# MaTouch_DevKit_1_28_Controller_V1_1.net
KiCad netlist of a schematic drawn in EAGLE
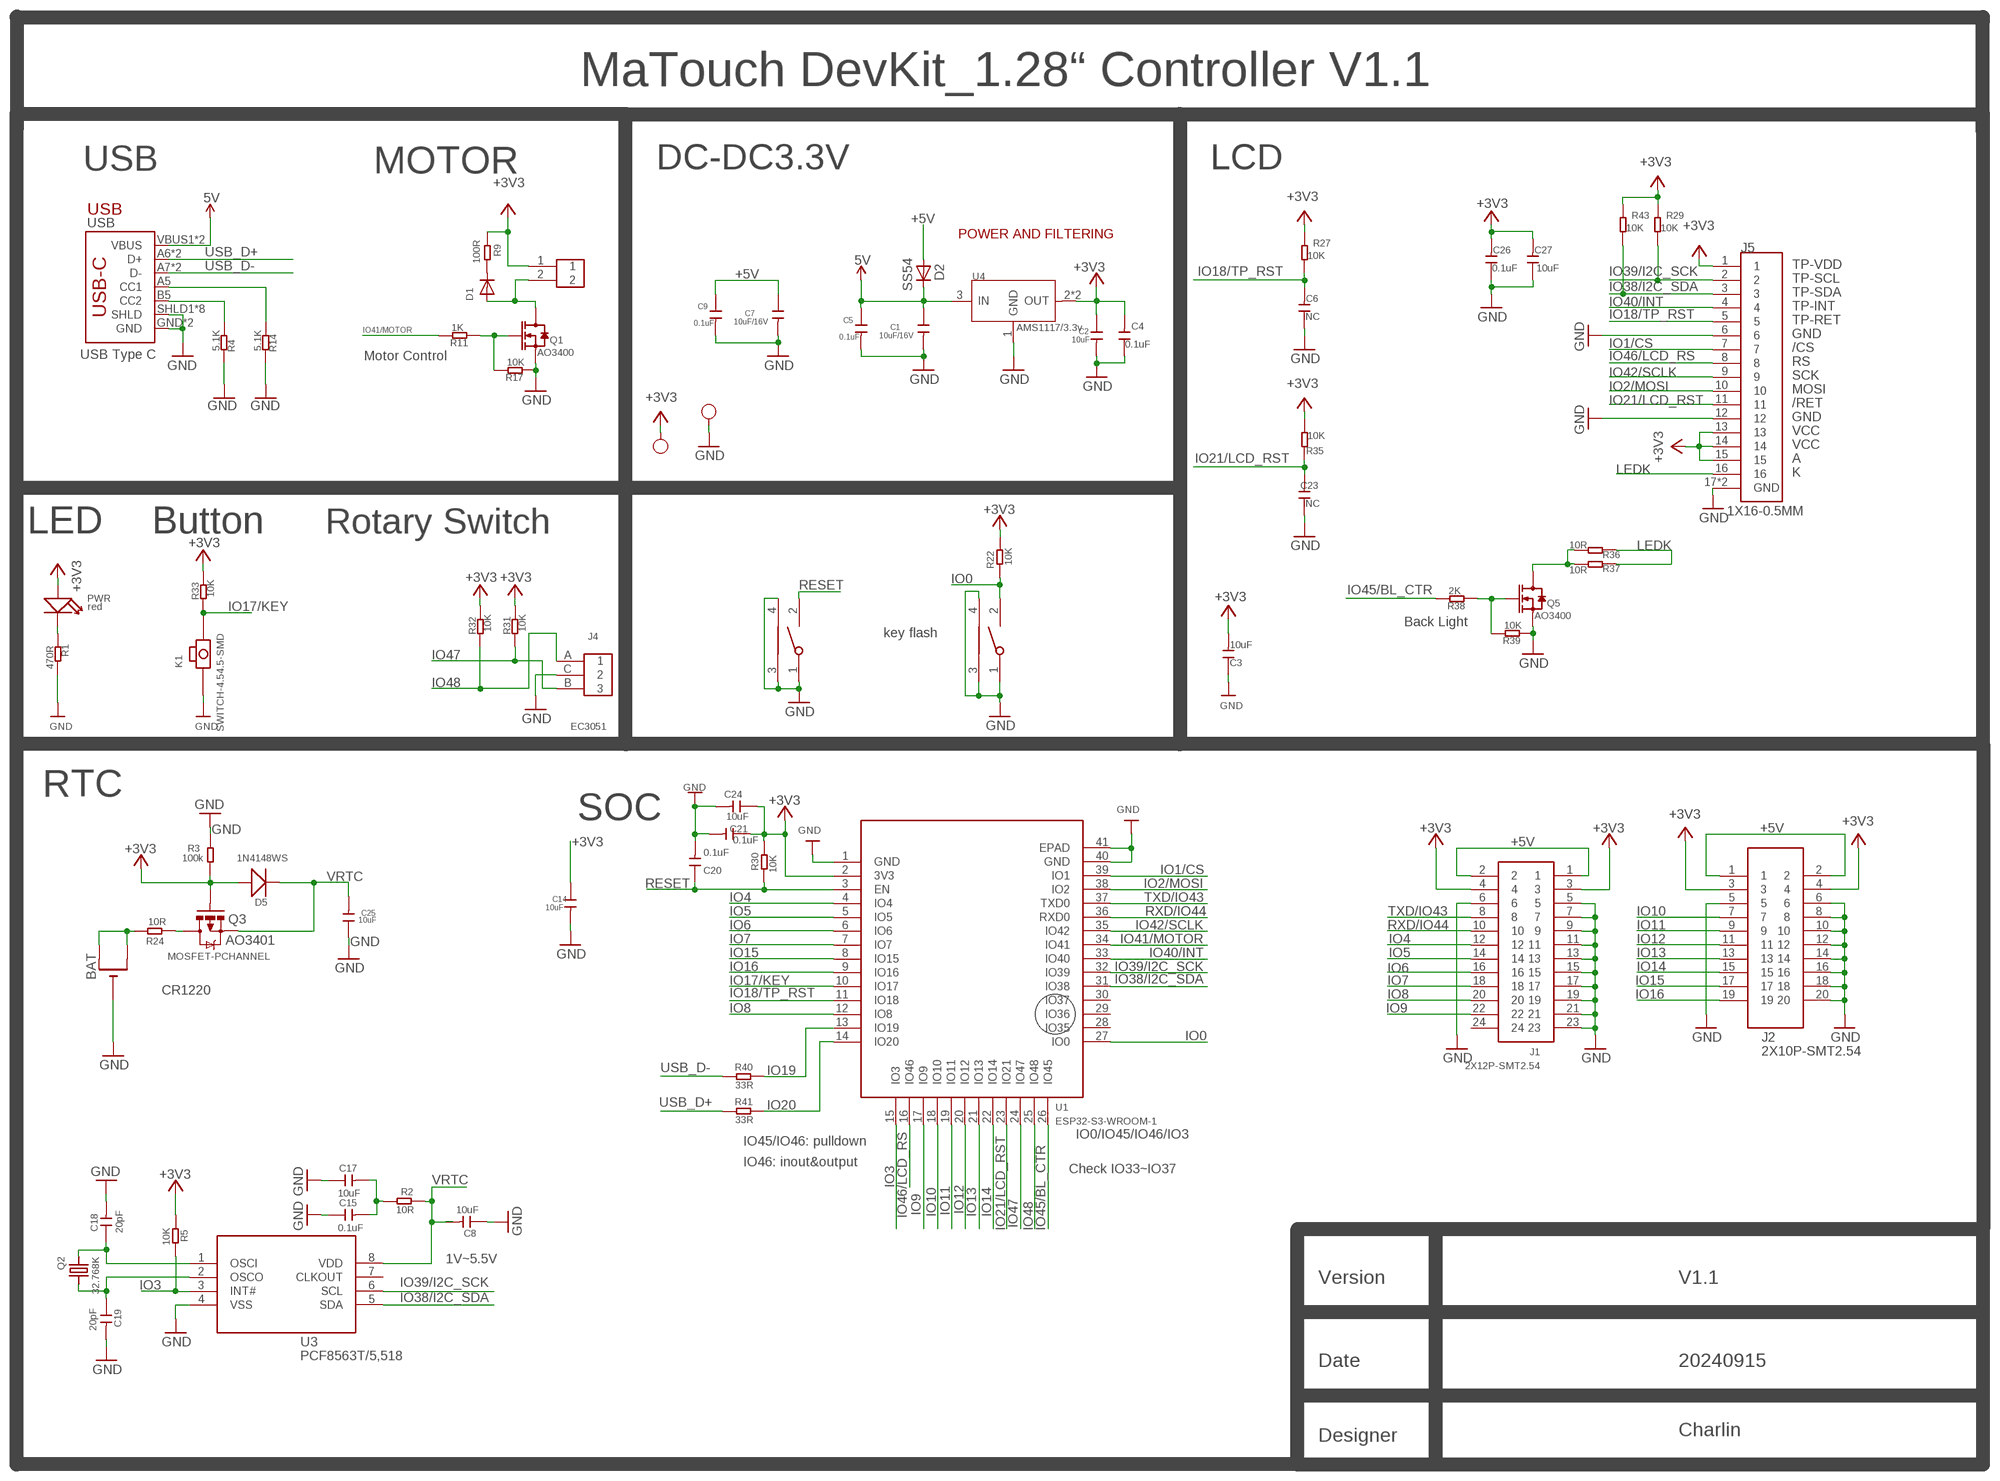
[diagram p0: schematic, sheet 1]

(export (version "E")
  (design (tool "Eeschema 10.0.6"))
  (components
    (comp (ref "3V3")
      (value "TEST-POINT'4545'")
      (footprint "eagle-import:TP-D45MIL")
      (fields (field (name "PARTNO") "DNP") (field (name "PARTNO_1") "DNP"))
      (libsource (lib "eagle-import") (part "TEST-POINT'4545'"))
    )
    (comp (ref "BAT")
      (value "CR1220SMT")
      (footprint "eagle-import:CR1220-SMD")
      (libsource (lib "eagle-import") (part "CR1220SMT"))
    )
    (comp (ref "BOOT")
      (value "TS24CA")
      (footprint "eagle-import:2_4_3.5MM")
      (libsource (lib "eagle-import") (part "TS24CA"))
    )
    (comp (ref "C1")
      (value "10uF/16V")
      (footprint "eagle-import:0603")
      (libsource (lib "eagle-import") (part "C-0603"))
    )
    (comp (ref "C2")
      (value "10uF")
      (footprint "eagle-import:0603")
      (libsource (lib "eagle-import") (part "C-0603"))
    )
    (comp (ref "C3")
      (value "10uF")
      (footprint "eagle-import:DISCRETE_C0603")
      (libsource (lib "eagle-import") (part "DISCRETE_C-0603"))
    )
    (comp (ref "C4")
      (value "0.1uF")
      (footprint "eagle-import:DISCRETE_C0402")
      (libsource (lib "eagle-import") (part "DISCRETE_C-0402"))
    )
    (comp (ref "C5")
      (value "0.1uF")
      (footprint "eagle-import:0603")
      (libsource (lib "eagle-import") (part "C-0603"))
    )
    (comp (ref "C6")
      (value "NC")
      (footprint "eagle-import:DISCRETE_C0402")
      (libsource (lib "eagle-import") (part "DISCRETE_C-0402"))
    )
    (comp (ref "C7")
      (value "10uF/16V")
      (footprint "eagle-import:0603")
      (libsource (lib "eagle-import") (part "C-0603"))
    )
    (comp (ref "C8")
      (value "10uF")
      (footprint "eagle-import:DISCRETE_C0603")
      (libsource (lib "eagle-import") (part "DISCRETE_C-0603"))
    )
    (comp (ref "C9")
      (value "0.1uF")
      (footprint "eagle-import:0603")
      (libsource (lib "eagle-import") (part "C-0603"))
    )
    (comp (ref "C14")
      (value "10uF")
      (footprint "eagle-import:0603")
      (libsource (lib "eagle-import") (part "C-0603"))
    )
    (comp (ref "C15")
      (value "0.1uF")
      (footprint "eagle-import:DISCRETE_C0603")
      (libsource (lib "eagle-import") (part "DISCRETE_C-0603"))
    )
    (comp (ref "C17")
      (value "10uF")
      (footprint "eagle-import:DISCRETE_C0603")
      (libsource (lib "eagle-import") (part "DISCRETE_C-0603"))
    )
    (comp (ref "C18")
      (value "20pF")
      (footprint "eagle-import:DISCRETE_C0603")
      (libsource (lib "eagle-import") (part "DISCRETE_C-0603"))
    )
    (comp (ref "C19")
      (value "20pF")
      (footprint "eagle-import:DISCRETE_C0603")
      (libsource (lib "eagle-import") (part "DISCRETE_C-0603"))
    )
    (comp (ref "C20")
      (value "0.1uF")
      (footprint "eagle-import:DISCRETE_C0603")
      (libsource (lib "eagle-import") (part "DISCRETE_C-0603"))
    )
    (comp (ref "C21")
      (value "0.1uF")
      (footprint "eagle-import:DISCRETE_C0603")
      (libsource (lib "eagle-import") (part "DISCRETE_C-0603"))
    )
    (comp (ref "C23")
      (value "NC")
      (footprint "eagle-import:DISCRETE_C0402")
      (libsource (lib "eagle-import") (part "DISCRETE_C-0402"))
    )
    (comp (ref "C24")
      (value "10uF")
      (footprint "eagle-import:DISCRETE_C0603")
      (libsource (lib "eagle-import") (part "DISCRETE_C-0603"))
    )
    (comp (ref "C25")
      (value "10uF")
      (footprint "eagle-import:0603")
      (libsource (lib "eagle-import") (part "C-0603"))
    )
    (comp (ref "C26")
      (value "0.1uF")
      (footprint "eagle-import:DISCRETE_C0402")
      (libsource (lib "eagle-import") (part "DISCRETE_C-0402"))
    )
    (comp (ref "C27")
      (value "10uF")
      (footprint "eagle-import:DISCRETE_C0402")
      (libsource (lib "eagle-import") (part "DISCRETE_C-0402"))
    )
    (comp (ref "D1")
      (value "DIODESOD-323F")
      (footprint "eagle-import:SOD-323F")
      (libsource (lib "eagle-import") (part "DIODESOD-323F"))
    )
    (comp (ref "D2")
      (value "SS54")
      (footprint "eagle-import:DO-214AC")
      (libsource (lib "eagle-import") (part "DIODE-DO-214AC"))
    )
    (comp (ref "D5")
      (value "1N4148WS")
      (footprint "eagle-import:SOD323")
      (libsource (lib "eagle-import") (part "D'0805'"))
    )
    (comp (ref "GND")
      (value "TEST-POINT'4545'")
      (footprint "eagle-import:TP-D45MIL")
      (fields (field (name "PARTNO") "DNP") (field (name "PARTNO_1") "DNP"))
      (libsource (lib "eagle-import") (part "TEST-POINT'4545'"))
    )
    (comp (ref "J1")
      (value "2X12P-SMT2.54")
      (footprint "eagle-import:2X12P-SMT2.54")
      (libsource (lib "eagle-import") (part "2X12P-SMT2.54"))
    )
    (comp (ref "J2")
      (value "2X10P-SMT2.54")
      (footprint "eagle-import:2X10P-SMT2.54")
      (libsource (lib "eagle-import") (part "2X10P-SMT2.54"))
    )
    (comp (ref "J4")
      (value "EC3051")
      (footprint "eagle-import:MAKERFABS_EC3051")
      (libsource (lib "eagle-import") (part "EC3051"))
    )
    (comp (ref "J5")
      (value "1X16-0.5MM")
      (footprint "eagle-import:1X16-0.5MM")
      (libsource (lib "eagle-import") (part "1X16-0.5MM"))
    )
    (comp (ref "K1")
      (value "SWITCH-4.54.5-SMD")
      (footprint "eagle-import:SWITCH-4.5_4.5-SMD")
      (libsource (lib "eagle-import") (part "SWITCH-4.54.5-SMD"))
    )
    (comp (ref "MOTOR")
      (value "CN-1.02P")
      (footprint "eagle-import:SH1.0-2P-SMD")
      (libsource (lib "eagle-import") (part "CN-1.02P"))
    )
    (comp (ref "PWR")
      (value "red")
      (footprint "eagle-import:DISCRETE_LED-0603")
      (libsource (lib "eagle-import") (part "DISCRETE_LED0603"))
    )
    (comp (ref "Q1")
      (value "AO3400")
      (footprint "eagle-import:SOT23@1")
      (libsource (lib "eagle-import") (part "MOSFET-N'SOT23'"))
    )
    (comp (ref "Q2")
      (value "32.768K")
      (footprint "eagle-import:XTAL3215")
      (libsource (lib "eagle-import") (part "CRYSTAL_3215"))
    )
    (comp (ref "Q3")
      (value "MOSFET-PCHANNEL")
      (footprint "eagle-import:SOT23-3")
      (libsource (lib "eagle-import") (part "MOSFET-PCHANNEL"))
    )
    (comp (ref "Q5")
      (value "AO3400")
      (footprint "eagle-import:SOT23@1")
      (libsource (lib "eagle-import") (part "MOSFET-N'SOT23'"))
    )
    (comp (ref "R1")
      (value "470R")
      (footprint "eagle-import:DISCRETE_R0402")
      (libsource (lib "eagle-import") (part "DISCRETE_R-0402"))
    )
    (comp (ref "R2")
      (value "10R")
      (footprint "eagle-import:R0603")
      (libsource (lib "eagle-import") (part "R-0603"))
    )
    (comp (ref "R3")
      (value "100k")
      (footprint "eagle-import:R0603")
      (libsource (lib "eagle-import") (part "R-0603"))
    )
    (comp (ref "R4")
      (value "5.1K")
      (footprint "eagle-import:DISCRETE_R0402")
      (libsource (lib "eagle-import") (part "DISCRETE_R-0402"))
    )
    (comp (ref "R5")
      (value "10K")
      (footprint "eagle-import:R0603")
      (libsource (lib "eagle-import") (part "R-0603"))
    )
    (comp (ref "R9")
      (value "100R")
      (footprint "eagle-import:DISCRETE_R0402")
      (libsource (lib "eagle-import") (part "DISCRETE_R-0402"))
    )
    (comp (ref "R11")
      (value "1K")
      (footprint "eagle-import:DISCRETE_R0402")
      (libsource (lib "eagle-import") (part "DISCRETE_R-0402"))
    )
    (comp (ref "R14")
      (value "5.1K")
      (footprint "eagle-import:DISCRETE_R0402")
      (libsource (lib "eagle-import") (part "DISCRETE_R-0402"))
    )
    (comp (ref "R17")
      (value "10K")
      (footprint "eagle-import:DISCRETE_R0402")
      (libsource (lib "eagle-import") (part "DISCRETE_R-0402"))
    )
    (comp (ref "R22")
      (value "10K")
      (footprint "eagle-import:R0603")
      (libsource (lib "eagle-import") (part "R-0603"))
    )
    (comp (ref "R24")
      (value "10R")
      (footprint "eagle-import:R0603")
      (libsource (lib "eagle-import") (part "R-0603"))
    )
    (comp (ref "R27")
      (value "10K")
      (footprint "eagle-import:DISCRETE_R0402")
      (libsource (lib "eagle-import") (part "DISCRETE_R-0402"))
    )
    (comp (ref "R29")
      (value "10K")
      (footprint "eagle-import:DISCRETE_R0402")
      (libsource (lib "eagle-import") (part "DISCRETE_R-0402"))
    )
    (comp (ref "R30")
      (value "10K")
      (footprint "eagle-import:R0603")
      (libsource (lib "eagle-import") (part "R-0603"))
    )
    (comp (ref "R31")
      (value "10K")
      (footprint "eagle-import:DISCRETE_R0402")
      (libsource (lib "eagle-import") (part "DISCRETE_R-0402"))
    )
    (comp (ref "R32")
      (value "10K")
      (footprint "eagle-import:DISCRETE_R0402")
      (libsource (lib "eagle-import") (part "DISCRETE_R-0402"))
    )
    (comp (ref "R33")
      (value "10K")
      (footprint "eagle-import:DISCRETE_R0402")
      (libsource (lib "eagle-import") (part "DISCRETE_R-0402"))
    )
    (comp (ref "R35")
      (value "10K")
      (footprint "eagle-import:DISCRETE_R0402")
      (libsource (lib "eagle-import") (part "DISCRETE_R-0402"))
    )
    (comp (ref "R36")
      (value "10R")
      (footprint "eagle-import:DISCRETE_R0402")
      (libsource (lib "eagle-import") (part "DISCRETE_R-0402"))
    )
    (comp (ref "R37")
      (value "10R")
      (footprint "eagle-import:DISCRETE_R0402")
      (libsource (lib "eagle-import") (part "DISCRETE_R-0402"))
    )
    (comp (ref "R38")
      (value "2K")
      (footprint "eagle-import:DISCRETE_R0402")
      (libsource (lib "eagle-import") (part "DISCRETE_R-0402"))
    )
    (comp (ref "R39")
      (value "10K")
      (footprint "eagle-import:DISCRETE_R0402")
      (libsource (lib "eagle-import") (part "DISCRETE_R-0402"))
    )
    (comp (ref "R40")
      (value "33R")
      (footprint "eagle-import:R0603")
      (libsource (lib "eagle-import") (part "R-0603"))
    )
    (comp (ref "R41")
      (value "33R")
      (footprint "eagle-import:R0603")
      (libsource (lib "eagle-import") (part "R-0603"))
    )
    (comp (ref "R43")
      (value "10K")
      (footprint "eagle-import:DISCRETE_R0402")
      (libsource (lib "eagle-import") (part "DISCRETE_R-0402"))
    )
    (comp (ref "RST")
      (value "TS24CA")
      (footprint "eagle-import:2_4_3.5MM")
      (libsource (lib "eagle-import") (part "TS24CA"))
    )
    (comp (ref "U1")
      (value "ESP32-S3-WROOM-1")
      (footprint "eagle-import:ESP32-S3-WROOM-1")
      (libsource (lib "eagle-import") (part "ESP32-S3-WROOM-1"))
    )
    (comp (ref "U3")
      (value "PCF8563T/5,518")
      (footprint "eagle-import:SOP8")
      (libsource (lib "eagle-import") (part "PCF8563T/5,518"))
    )
    (comp (ref "U4")
      (value "AMS1117/3.3v")
      (footprint "eagle-import:SOT89")
      (libsource (lib "eagle-import") (part "LD1117'SOT89'"))
    )
    (comp (ref "USB")
      (value "USB_C5")
      (footprint "eagle-import:USB-C-16P-5")
      (libsource (lib "eagle-import") (part "USB_C5"))
    )
  )
  (nets
    (net (code "1") (name "+3V3") (class "Default")
      (node (ref "3V3") (pin "T") (pinfunction "T_T") (pintype "bidirectional"))
      (node (ref "C14") (pin "1") (pinfunction "1_1") (pintype "passive"))
      (node (ref "C2") (pin "1") (pinfunction "1_1") (pintype "passive"))
      (node (ref "C21") (pin "1") (pinfunction "1_1") (pintype "passive"))
      (node (ref "C24") (pin "1") (pinfunction "1_1") (pintype "passive"))
      (node (ref "C26") (pin "2") (pinfunction "2_2") (pintype "passive"))
      (node (ref "C27") (pin "2") (pinfunction "2_2") (pintype "passive"))
      (node (ref "C3") (pin "2") (pinfunction "2_2") (pintype "passive"))
      (node (ref "C4") (pin "2") (pinfunction "2_2") (pintype "passive"))
      (node (ref "D5") (pin "+") (pinfunction "+_+") (pintype "passive"))
      (node (ref "J1") (pin "3") (pinfunction "3_3") (pintype "bidirectional"))
      (node (ref "J1") (pin "4") (pinfunction "4_4") (pintype "bidirectional"))
      (node (ref "J2") (pin "3") (pinfunction "3_3") (pintype "bidirectional"))
      (node (ref "J2") (pin "4") (pinfunction "4_4") (pintype "bidirectional"))
      (node (ref "J5") (pin "1") (pinfunction "1_1") (pintype "bidirectional"))
      (node (ref "J5") (pin "13") (pinfunction "13_13") (pintype "bidirectional"))
      (node (ref "J5") (pin "14") (pinfunction "14_14") (pintype "bidirectional"))
      (node (ref "J5") (pin "15") (pinfunction "15_15") (pintype "bidirectional"))
      (node (ref "MOTOR") (pin "1") (pinfunction "1_1") (pintype "bidirectional"))
      (node (ref "PWR") (pin "+") (pinfunction "+_+") (pintype "passive"))
      (node (ref "Q3") (pin "1") (pinfunction "G_1") (pintype "passive"))
      (node (ref "R22") (pin "2") (pinfunction "2_2") (pintype "passive"))
      (node (ref "R27") (pin "2") (pinfunction "2_2") (pintype "passive"))
      (node (ref "R29") (pin "2") (pinfunction "2_2") (pintype "passive"))
      (node (ref "R3") (pin "1") (pinfunction "1_1") (pintype "passive"))
      (node (ref "R30") (pin "2") (pinfunction "2_2") (pintype "passive"))
      (node (ref "R31") (pin "1") (pinfunction "1_1") (pintype "passive"))
      (node (ref "R32") (pin "1") (pinfunction "1_1") (pintype "passive"))
      (node (ref "R33") (pin "1") (pinfunction "1_1") (pintype "passive"))
      (node (ref "R35") (pin "2") (pinfunction "2_2") (pintype "passive"))
      (node (ref "R43") (pin "2") (pinfunction "2_2") (pintype "passive"))
      (node (ref "R5") (pin "1") (pinfunction "1_1") (pintype "passive"))
      (node (ref "R9") (pin "1") (pinfunction "1_1") (pintype "passive"))
      (node (ref "U1") (pin "2") (pinfunction "3V3_2") (pintype "bidirectional"))
      (node (ref "U4") (pin "2") (pinfunction "OUT_2") (pintype "bidirectional"))
      (node (ref "U4") (pin "4") (pinfunction "OUT_4") (pintype "bidirectional"))
    )
    (net (code "2") (name "/+5V") (class "Default")
      (node (ref "C7") (pin "1") (pinfunction "1_1") (pintype "passive"))
      (node (ref "C9") (pin "1") (pinfunction "1_1") (pintype "passive"))
      (node (ref "D2") (pin "A") (pinfunction "A_A") (pintype "passive"))
      (node (ref "J1") (pin "1") (pinfunction "1_1") (pintype "bidirectional"))
      (node (ref "J1") (pin "2") (pinfunction "2_2") (pintype "bidirectional"))
      (node (ref "J2") (pin "1") (pinfunction "1_1") (pintype "bidirectional"))
      (node (ref "J2") (pin "2") (pinfunction "2_2") (pintype "bidirectional"))
    )
    (net (code "3") (name "/IO0") (class "Default")
      (node (ref "BOOT") (pin "2") (pinfunction "2_2") (pintype "bidirectional"))
      (node (ref "R22") (pin "1") (pinfunction "1_1") (pintype "passive"))
      (node (ref "U1") (pin "27") (pinfunction "IO0_27") (pintype "bidirectional"))
    )
    (net (code "4") (name "/IO1{slash}CS") (class "Default")
      (node (ref "J5") (pin "7") (pinfunction "7_7") (pintype "bidirectional"))
      (node (ref "U1") (pin "39") (pinfunction "IO1_39") (pintype "bidirectional"))
    )
    (net (code "5") (name "/IO2{slash}MOSI") (class "Default")
      (node (ref "J5") (pin "10") (pinfunction "10_10") (pintype "bidirectional"))
      (node (ref "U1") (pin "38") (pinfunction "IO2_38") (pintype "bidirectional"))
    )
    (net (code "6") (name "/IO3") (class "Default")
      (node (ref "R5") (pin "2") (pinfunction "2_2") (pintype "passive"))
      (node (ref "U1") (pin "15") (pinfunction "IO3_15") (pintype "bidirectional"))
      (node (ref "U3") (pin "3") (pinfunction "INT#_3") (pintype "bidirectional"))
    )
    (net (code "7") (name "/IO4") (class "Default")
      (node (ref "J1") (pin "12") (pinfunction "12_12") (pintype "bidirectional"))
      (node (ref "U1") (pin "4") (pinfunction "IO4_4") (pintype "bidirectional"))
    )
    (net (code "8") (name "/IO5") (class "Default")
      (node (ref "J1") (pin "14") (pinfunction "14_14") (pintype "bidirectional"))
      (node (ref "U1") (pin "5") (pinfunction "IO5_5") (pintype "bidirectional"))
    )
    (net (code "9") (name "/IO6") (class "Default")
      (node (ref "J1") (pin "16") (pinfunction "16_16") (pintype "bidirectional"))
      (node (ref "U1") (pin "6") (pinfunction "IO6_6") (pintype "bidirectional"))
    )
    (net (code "10") (name "/IO7") (class "Default")
      (node (ref "J1") (pin "18") (pinfunction "18_18") (pintype "bidirectional"))
      (node (ref "U1") (pin "7") (pinfunction "IO7_7") (pintype "bidirectional"))
    )
    (net (code "11") (name "/IO8") (class "Default")
      (node (ref "J1") (pin "20") (pinfunction "20_20") (pintype "bidirectional"))
      (node (ref "U1") (pin "12") (pinfunction "IO8_12") (pintype "bidirectional"))
    )
    (net (code "12") (name "/IO9") (class "Default")
      (node (ref "J1") (pin "22") (pinfunction "22_22") (pintype "bidirectional"))
      (node (ref "U1") (pin "17") (pinfunction "IO9_17") (pintype "bidirectional"))
    )
    (net (code "13") (name "/IO10") (class "Default")
      (node (ref "J2") (pin "7") (pinfunction "7_7") (pintype "bidirectional"))
      (node (ref "U1") (pin "18") (pinfunction "IO10_18") (pintype "bidirectional"))
    )
    (net (code "14") (name "/IO11") (class "Default")
      (node (ref "J2") (pin "9") (pinfunction "9_9") (pintype "bidirectional"))
      (node (ref "U1") (pin "19") (pinfunction "IO11_19") (pintype "bidirectional"))
    )
    (net (code "15") (name "/IO12") (class "Default")
      (node (ref "J2") (pin "11") (pinfunction "11_11") (pintype "bidirectional"))
      (node (ref "U1") (pin "20") (pinfunction "IO12_20") (pintype "bidirectional"))
    )
    (net (code "16") (name "/IO13") (class "Default")
      (node (ref "J2") (pin "13") (pinfunction "13_13") (pintype "bidirectional"))
      (node (ref "U1") (pin "21") (pinfunction "IO13_21") (pintype "bidirectional"))
    )
    (net (code "17") (name "/IO14") (class "Default")
      (node (ref "J2") (pin "15") (pinfunction "15_15") (pintype "bidirectional"))
      (node (ref "U1") (pin "22") (pinfunction "IO14_22") (pintype "bidirectional"))
    )
    (net (code "18") (name "/IO15") (class "Default")
      (node (ref "J2") (pin "17") (pinfunction "17_17") (pintype "bidirectional"))
      (node (ref "U1") (pin "8") (pinfunction "IO15_8") (pintype "bidirectional"))
    )
    (net (code "19") (name "/IO16") (class "Default")
      (node (ref "J2") (pin "19") (pinfunction "19_19") (pintype "bidirectional"))
      (node (ref "U1") (pin "9") (pinfunction "IO16_9") (pintype "bidirectional"))
    )
    (net (code "20") (name "/IO17{slash}KEY") (class "Default")
      (node (ref "K1") (pin "2") (pinfunction "2_2") (pintype "bidirectional"))
      (node (ref "K1") (pin "3") (pinfunction "2_3") (pintype "bidirectional"))
      (node (ref "R33") (pin "2") (pinfunction "2_2") (pintype "passive"))
      (node (ref "U1") (pin "10") (pinfunction "IO17_10") (pintype "bidirectional"))
    )
    (net (code "21") (name "/IO18{slash}TP_RST") (class "Default")
      (node (ref "C6") (pin "2") (pinfunction "2_2") (pintype "passive"))
      (node (ref "J5") (pin "5") (pinfunction "5_5") (pintype "bidirectional"))
      (node (ref "R27") (pin "1") (pinfunction "1_1") (pintype "passive"))
      (node (ref "U1") (pin "11") (pinfunction "IO18_11") (pintype "bidirectional"))
    )
    (net (code "22") (name "/IO19") (class "Default")
      (node (ref "R40") (pin "2") (pinfunction "2_2") (pintype "passive"))
      (node (ref "U1") (pin "13") (pinfunction "IO19_13") (pintype "bidirectional"))
    )
    (net (code "23") (name "/IO20") (class "Default")
      (node (ref "R41") (pin "2") (pinfunction "2_2") (pintype "passive"))
      (node (ref "U1") (pin "14") (pinfunction "IO20_14") (pintype "bidirectional"))
    )
    (net (code "24") (name "/IO21{slash}LCD_RST") (class "Default")
      (node (ref "C23") (pin "2") (pinfunction "2_2") (pintype "passive"))
      (node (ref "J5") (pin "11") (pinfunction "11_11") (pintype "bidirectional"))
      (node (ref "R35") (pin "1") (pinfunction "1_1") (pintype "passive"))
      (node (ref "U1") (pin "23") (pinfunction "IO21_23") (pintype "bidirectional"))
    )
    (net (code "25") (name "/IO38{slash}I2C_SDA") (class "Default")
      (node (ref "J5") (pin "3") (pinfunction "3_3") (pintype "bidirectional"))
      (node (ref "R43") (pin "1") (pinfunction "1_1") (pintype "passive"))
      (node (ref "U1") (pin "31") (pinfunction "IO38_31") (pintype "bidirectional"))
      (node (ref "U3") (pin "5") (pinfunction "SDA_5") (pintype "bidirectional"))
    )
    (net (code "26") (name "/IO39{slash}I2C_SCK") (class "Default")
      (node (ref "J5") (pin "2") (pinfunction "2_2") (pintype "bidirectional"))
      (node (ref "R29") (pin "1") (pinfunction "1_1") (pintype "passive"))
      (node (ref "U1") (pin "32") (pinfunction "IO39_32") (pintype "bidirectional"))
      (node (ref "U3") (pin "6") (pinfunction "SCL_6") (pintype "bidirectional"))
    )
    (net (code "27") (name "/IO40{slash}INT") (class "Default")
      (node (ref "J5") (pin "4") (pinfunction "4_4") (pintype "bidirectional"))
      (node (ref "U1") (pin "33") (pinfunction "IO40_33") (pintype "bidirectional"))
    )
    (net (code "28") (name "/IO41{slash}MOTOR") (class "Default")
      (node (ref "R11") (pin "2") (pinfunction "2_2") (pintype "passive"))
      (node (ref "U1") (pin "34") (pinfunction "IO41_34") (pintype "bidirectional"))
    )
    (net (code "29") (name "/IO42{slash}SCLK") (class "Default")
      (node (ref "J5") (pin "9") (pinfunction "9_9") (pintype "bidirectional"))
      (node (ref "U1") (pin "35") (pinfunction "IO42_35") (pintype "bidirectional"))
    )
    (net (code "30") (name "/IO45{slash}BL_CTR") (class "Default")
      (node (ref "R38") (pin "2") (pinfunction "2_2") (pintype "passive"))
      (node (ref "U1") (pin "26") (pinfunction "IO45_26") (pintype "bidirectional"))
    )
    (net (code "31") (name "/IO46{slash}LCD_RS") (class "Default")
      (node (ref "J5") (pin "8") (pinfunction "8_8") (pintype "bidirectional"))
      (node (ref "U1") (pin "16") (pinfunction "IO46_16") (pintype "bidirectional"))
    )
    (net (code "32") (name "/IO47") (class "Default")
      (node (ref "J4") (pin "B") (pinfunction "3_B") (pintype "bidirectional"))
      (node (ref "R31") (pin "2") (pinfunction "2_2") (pintype "passive"))
      (node (ref "U1") (pin "24") (pinfunction "IO47_24") (pintype "bidirectional"))
    )
    (net (code "33") (name "/IO48") (class "Default")
      (node (ref "J4") (pin "A") (pinfunction "1_A") (pintype "bidirectional"))
      (node (ref "R32") (pin "2") (pinfunction "2_2") (pintype "passive"))
      (node (ref "U1") (pin "25") (pinfunction "IO48_25") (pintype "bidirectional"))
    )
    (net (code "34") (name "/LEDK") (class "Default")
      (node (ref "J5") (pin "16") (pinfunction "16_16") (pintype "bidirectional"))
      (node (ref "R36") (pin "1") (pinfunction "1_1") (pintype "passive"))
      (node (ref "R37") (pin "1") (pinfunction "1_1") (pintype "passive"))
    )
    (net (code "35") (name "/RESET") (class "Default")
      (node (ref "C20") (pin "1") (pinfunction "1_1") (pintype "passive"))
      (node (ref "R30") (pin "1") (pinfunction "1_1") (pintype "passive"))
      (node (ref "RST") (pin "2") (pinfunction "2_2") (pintype "bidirectional"))
      (node (ref "U1") (pin "3") (pinfunction "EN_3") (pintype "bidirectional"))
    )
    (net (code "36") (name "/RXD{slash}IO44") (class "Default")
      (node (ref "J1") (pin "10") (pinfunction "10_10") (pintype "bidirectional"))
      (node (ref "U1") (pin "36") (pinfunction "RXD0_36") (pintype "bidirectional"))
    )
    (net (code "37") (name "/TXD{slash}IO43") (class "Default")
      (node (ref "J1") (pin "8") (pinfunction "8_8") (pintype "bidirectional"))
      (node (ref "U1") (pin "37") (pinfunction "TXD0_37") (pintype "bidirectional"))
    )
    (net (code "38") (name "/USB_D+") (class "Default")
      (node (ref "R41") (pin "1") (pinfunction "1_1") (pintype "passive"))
      (node (ref "USB") (pin "A6") (pinfunction "D+_A6") (pintype "bidirectional"))
      (node (ref "USB") (pin "B6") (pinfunction "D+_B6") (pintype "bidirectional"))
    )
    (net (code "39") (name "/USB_D-") (class "Default")
      (node (ref "R40") (pin "1") (pinfunction "1_1") (pintype "passive"))
      (node (ref "USB") (pin "A7") (pinfunction "D-_A7") (pintype "bidirectional"))
      (node (ref "USB") (pin "B7") (pinfunction "D-_B7") (pintype "bidirectional"))
    )
    (net (code "40") (name "/VRTC") (class "Default")
      (node (ref "C25") (pin "2") (pinfunction "2_2") (pintype "passive"))
      (node (ref "C8") (pin "2") (pinfunction "2_2") (pintype "passive"))
      (node (ref "D5") (pin "-") (pinfunction "-_-") (pintype "passive"))
      (node (ref "Q3") (pin "2") (pinfunction "S_2") (pintype "passive"))
      (node (ref "R2") (pin "2") (pinfunction "2_2") (pintype "passive"))
      (node (ref "U3") (pin "8") (pinfunction "VDD_8") (pintype "bidirectional"))
    )
    (net (code "41") (name "5V") (class "Default")
      (node (ref "C1") (pin "1") (pinfunction "1_1") (pintype "passive"))
      (node (ref "C5") (pin "1") (pinfunction "1_1") (pintype "passive"))
      (node (ref "D2") (pin "C") (pinfunction "C_C") (pintype "passive"))
      (node (ref "U4") (pin "3") (pinfunction "IN_3") (pintype "bidirectional"))
      (node (ref "USB") (pin "VBUS1") (pinfunction "VBUS_VBUS1") (pintype "bidirectional"))
      (node (ref "USB") (pin "VBUS2") (pinfunction "VBUS_VBUS2") (pintype "bidirectional"))
    )
    (net (code "42") (name "GND") (class "Default")
      (node (ref "BAT") (pin "-") (pinfunction "-_-") (pintype "passive"))
      (node (ref "BOOT") (pin "1") (pinfunction "1_1") (pintype "bidirectional"))
      (node (ref "BOOT") (pin "3") (pinfunction "3_3") (pintype "bidirectional"))
      (node (ref "BOOT") (pin "4") (pinfunction "4_4") (pintype "bidirectional"))
      (node (ref "C1") (pin "2") (pinfunction "2_2") (pintype "passive"))
      (node (ref "C14") (pin "2") (pinfunction "2_2") (pintype "passive"))
      (node (ref "C15") (pin "1") (pinfunction "1_1") (pintype "passive"))
      (node (ref "C17") (pin "1") (pinfunction "1_1") (pintype "passive"))
      (node (ref "C18") (pin "2") (pinfunction "2_2") (pintype "passive"))
      (node (ref "C19") (pin "2") (pinfunction "2_2") (pintype "passive"))
      (node (ref "C2") (pin "2") (pinfunction "2_2") (pintype "passive"))
      (node (ref "C20") (pin "2") (pinfunction "2_2") (pintype "passive"))
      (node (ref "C21") (pin "2") (pinfunction "2_2") (pintype "passive"))
      (node (ref "C23") (pin "1") (pinfunction "1_1") (pintype "passive"))
      (node (ref "C24") (pin "2") (pinfunction "2_2") (pintype "passive"))
      (node (ref "C25") (pin "1") (pinfunction "1_1") (pintype "passive"))
      (node (ref "C26") (pin "1") (pinfunction "1_1") (pintype "passive"))
      (node (ref "C27") (pin "1") (pinfunction "1_1") (pintype "passive"))
      (node (ref "C3") (pin "1") (pinfunction "1_1") (pintype "passive"))
      (node (ref "C4") (pin "1") (pinfunction "1_1") (pintype "passive"))
      (node (ref "C5") (pin "2") (pinfunction "2_2") (pintype "passive"))
      (node (ref "C6") (pin "1") (pinfunction "1_1") (pintype "passive"))
      (node (ref "C7") (pin "2") (pinfunction "2_2") (pintype "passive"))
      (node (ref "C8") (pin "1") (pinfunction "1_1") (pintype "passive"))
      (node (ref "C9") (pin "2") (pinfunction "2_2") (pintype "passive"))
      (node (ref "GND") (pin "T") (pinfunction "T_T") (pintype "bidirectional"))
      (node (ref "J1") (pin "11") (pinfunction "11_11") (pintype "bidirectional"))
      (node (ref "J1") (pin "13") (pinfunction "13_13") (pintype "bidirectional"))
      (node (ref "J1") (pin "15") (pinfunction "15_15") (pintype "bidirectional"))
      (node (ref "J1") (pin "17") (pinfunction "17_17") (pintype "bidirectional"))
      (node (ref "J1") (pin "19") (pinfunction "19_19") (pintype "bidirectional"))
      (node (ref "J1") (pin "21") (pinfunction "21_21") (pintype "bidirectional"))
      (node (ref "J1") (pin "23") (pinfunction "23_23") (pintype "bidirectional"))
      (node (ref "J1") (pin "5") (pinfunction "5_5") (pintype "bidirectional"))
      (node (ref "J1") (pin "6") (pinfunction "6_6") (pintype "bidirectional"))
      (node (ref "J1") (pin "7") (pinfunction "7_7") (pintype "bidirectional"))
      (node (ref "J1") (pin "9") (pinfunction "9_9") (pintype "bidirectional"))
      (node (ref "J2") (pin "10") (pinfunction "10_10") (pintype "bidirectional"))
      (node (ref "J2") (pin "12") (pinfunction "12_12") (pintype "bidirectional"))
      (node (ref "J2") (pin "14") (pinfunction "14_14") (pintype "bidirectional"))
      (node (ref "J2") (pin "16") (pinfunction "16_16") (pintype "bidirectional"))
      (node (ref "J2") (pin "18") (pinfunction "18_18") (pintype "bidirectional"))
      (node (ref "J2") (pin "20") (pinfunction "20_20") (pintype "bidirectional"))
      (node (ref "J2") (pin "5") (pinfunction "5_5") (pintype "bidirectional"))
      (node (ref "J2") (pin "6") (pinfunction "6_6") (pintype "bidirectional"))
      (node (ref "J2") (pin "8") (pinfunction "8_8") (pintype "bidirectional"))
      (node (ref "J4") (pin "C") (pinfunction "2_C") (pintype "bidirectional"))
      (node (ref "J5") (pin "12") (pinfunction "12_12") (pintype "bidirectional"))
      (node (ref "J5") (pin "17") (pinfunction "GND_17") (pintype "bidirectional"))
      (node (ref "J5") (pin "18") (pinfunction "GND_18") (pintype "bidirectional"))
      (node (ref "J5") (pin "6") (pinfunction "6_6") (pintype "bidirectional"))
      (node (ref "K1") (pin "1") (pinfunction "1_1") (pintype "bidirectional"))
      (node (ref "K1") (pin "4") (pinfunction "1_4") (pintype "bidirectional"))
      (node (ref "Q1") (pin "2") (pinfunction "S_2") (pintype "passive"))
      (node (ref "Q5") (pin "2") (pinfunction "S_2") (pintype "passive"))
      (node (ref "R1") (pin "1") (pinfunction "1_1") (pintype "passive"))
      (node (ref "R14") (pin "2") (pinfunction "2_2") (pintype "passive"))
      (node (ref "R17") (pin "1") (pinfunction "1_1") (pintype "passive"))
      (node (ref "R3") (pin "2") (pinfunction "2_2") (pintype "passive"))
      (node (ref "R39") (pin "1") (pinfunction "1_1") (pintype "passive"))
      (node (ref "R4") (pin "2") (pinfunction "2_2") (pintype "passive"))
      (node (ref "RST") (pin "1") (pinfunction "1_1") (pintype "bidirectional"))
      (node (ref "RST") (pin "3") (pinfunction "3_3") (pintype "bidirectional"))
      (node (ref "RST") (pin "4") (pinfunction "4_4") (pintype "bidirectional"))
      (node (ref "U1") (pin "1") (pinfunction "GND_1") (pintype "bidirectional"))
      (node (ref "U1") (pin "40") (pinfunction "GND_40") (pintype "bidirectional"))
      (node (ref "U1") (pin "41") (pinfunction "EPAD_41") (pintype "bidirectional"))
      (node (ref "U3") (pin "4") (pinfunction "VSS_4") (pintype "bidirectional"))
      (node (ref "U4") (pin "1") (pinfunction "GND_1") (pintype "bidirectional"))
      (node (ref "USB") (pin "GND") (pinfunction "GND_GND") (pintype "bidirectional"))
      (node (ref "USB") (pin "GND2") (pinfunction "GND_GND2") (pintype "bidirectional"))
      (node (ref "USB") (pin "SHLD1") (pinfunction "SHLD_SHLD1") (pintype "bidirectional"))
      (node (ref "USB") (pin "SHLD2") (pinfunction "SHLD_SHLD2") (pintype "bidirectional"))
      (node (ref "USB") (pin "SHLD3") (pinfunction "SHLD_SHLD3") (pintype "bidirectional"))
      (node (ref "USB") (pin "SHLD4") (pinfunction "SHLD_SHLD4") (pintype "bidirectional"))
      (node (ref "USB") (pin "SHLD5") (pinfunction "SHLD_SHLD5") (pintype "bidirectional"))
      (node (ref "USB") (pin "SHLD6") (pinfunction "SHLD_SHLD6") (pintype "bidirectional"))
      (node (ref "USB") (pin "SHLD7") (pinfunction "SHLD_SHLD7") (pintype "bidirectional"))
      (node (ref "USB") (pin "SHLD8") (pinfunction "SHLD_SHLD8") (pintype "bidirectional"))
    )
    (net (code "43") (name "Net-(BAT-+)") (class "Default")
      (node (ref "BAT") (pin "+$1") (pinfunction "+_+$1") (pintype "passive"))
      (node (ref "BAT") (pin "+$2") (pinfunction "+1_+$2") (pintype "passive"))
      (node (ref "R24") (pin "2") (pinfunction "2_2") (pintype "passive"))
    )
    (net (code "44") (name "Net-(C15-Pad2)") (class "Default")
      (node (ref "C15") (pin "2") (pinfunction "2_2") (pintype "passive"))
      (node (ref "C17") (pin "2") (pinfunction "2_2") (pintype "passive"))
      (node (ref "R2") (pin "1") (pinfunction "1_1") (pintype "passive"))
    )
    (net (code "45") (name "Net-(D1-PadC)") (class "Default")
      (node (ref "D1") (pin "C") (pinfunction "C_C") (pintype "passive"))
      (node (ref "R9") (pin "2") (pinfunction "2_2") (pintype "passive"))
    )
    (net (code "46") (name "Net-(PWR-Pad-)") (class "Default")
      (node (ref "PWR") (pin "-") (pinfunction "-_-") (pintype "passive"))
      (node (ref "R1") (pin "2") (pinfunction "2_2") (pintype "passive"))
    )
    (net (code "47") (name "Net-(Q1-D)") (class "Default")
      (node (ref "D1") (pin "A") (pinfunction "A_A") (pintype "passive"))
      (node (ref "MOTOR") (pin "2") (pinfunction "2_2") (pintype "bidirectional"))
      (node (ref "Q1") (pin "3") (pinfunction "D_3") (pintype "passive"))
    )
    (net (code "48") (name "Net-(Q1-G)") (class "Default")
      (node (ref "Q1") (pin "1") (pinfunction "G_1") (pintype "passive"))
      (node (ref "R11") (pin "1") (pinfunction "1_1") (pintype "passive"))
      (node (ref "R17") (pin "2") (pinfunction "2_2") (pintype "passive"))
    )
    (net (code "49") (name "Net-(Q2-1)") (class "Default")
      (node (ref "C18") (pin "1") (pinfunction "1_1") (pintype "passive"))
      (node (ref "Q2") (pin "P$1") (pinfunction "1_P$1") (pintype "passive"))
      (node (ref "U3") (pin "1") (pinfunction "OSCI_1") (pintype "bidirectional"))
    )
    (net (code "50") (name "Net-(Q2-2)") (class "Default")
      (node (ref "C19") (pin "1") (pinfunction "1_1") (pintype "passive"))
      (node (ref "Q2") (pin "P$2") (pinfunction "2_P$2") (pintype "passive"))
      (node (ref "U3") (pin "2") (pinfunction "OSCO_2") (pintype "bidirectional"))
    )
    (net (code "51") (name "Net-(Q3-D)") (class "Default")
      (node (ref "Q3") (pin "3") (pinfunction "D_3") (pintype "passive"))
      (node (ref "R24") (pin "1") (pinfunction "1_1") (pintype "passive"))
    )
    (net (code "52") (name "Net-(Q5-D)") (class "Default")
      (node (ref "Q5") (pin "3") (pinfunction "D_3") (pintype "passive"))
      (node (ref "R36") (pin "2") (pinfunction "2_2") (pintype "passive"))
      (node (ref "R37") (pin "2") (pinfunction "2_2") (pintype "passive"))
    )
    (net (code "53") (name "Net-(Q5-G)") (class "Default")
      (node (ref "Q5") (pin "1") (pinfunction "G_1") (pintype "passive"))
      (node (ref "R38") (pin "1") (pinfunction "1_1") (pintype "passive"))
      (node (ref "R39") (pin "2") (pinfunction "2_2") (pintype "passive"))
    )
    (net (code "54") (name "Net-(USB-CC1)") (class "Default")
      (node (ref "R14") (pin "1") (pinfunction "1_1") (pintype "passive"))
      (node (ref "USB") (pin "A5") (pinfunction "CC1_A5") (pintype "bidirectional"))
    )
    (net (code "55") (name "Net-(USB-CC2)") (class "Default")
      (node (ref "R4") (pin "1") (pinfunction "1_1") (pintype "passive"))
      (node (ref "USB") (pin "B5") (pinfunction "CC2_B5") (pintype "bidirectional"))
    )
    (net (code "56") (name "unconnected-(J1-Pad24)") (class "Default")
      (node (ref "J1") (pin "24") (pinfunction "24_24") (pintype "bidirectional"))
    )
    (net (code "57") (name "unconnected-(U1-IO35-Pad28)") (class "Default")
      (node (ref "U1") (pin "28") (pinfunction "IO35_28") (pintype "bidirectional"))
    )
    (net (code "58") (name "unconnected-(U1-IO36-Pad29)") (class "Default")
      (node (ref "U1") (pin "29") (pinfunction "IO36_29") (pintype "bidirectional"))
    )
    (net (code "59") (name "unconnected-(U1-IO37-Pad30)") (class "Default")
      (node (ref "U1") (pin "30") (pinfunction "IO37_30") (pintype "bidirectional"))
    )
    (net (code "60") (name "unconnected-(U3-CLKOUT-Pad7)") (class "Default")
      (node (ref "U3") (pin "7") (pinfunction "CLKOUT_7") (pintype "bidirectional"))
    )
  )
)
